# NEWLED.net
KiCad netlist of a schematic drawn in Altium Designer
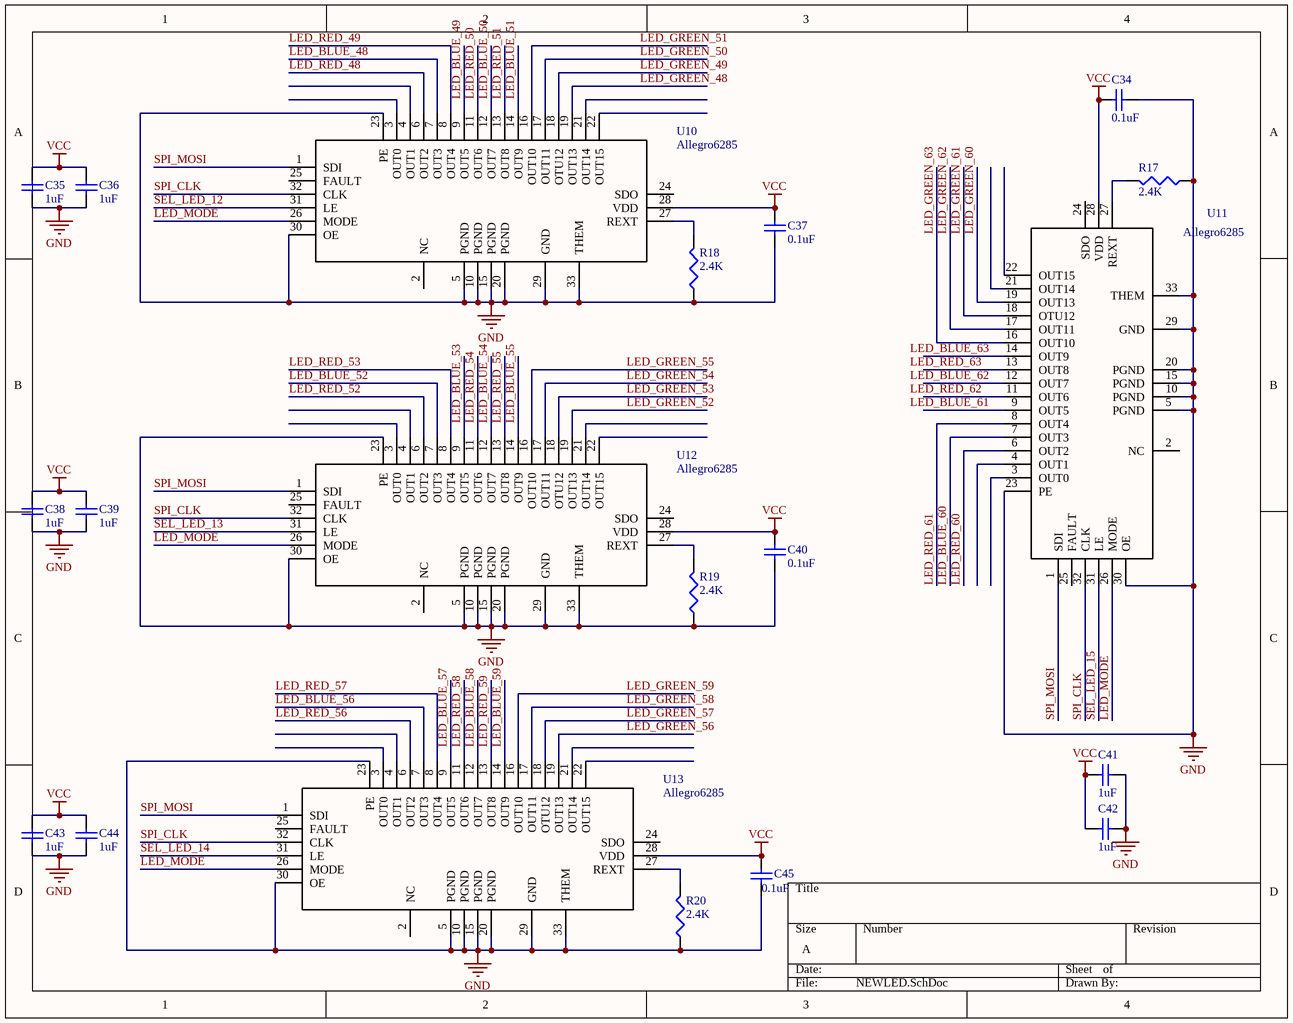
[diagram p0: NEWLED.SchDoc]

(export (version "E")
  (design (tool "Eeschema 10.0.6"))
  (components
    (comp (ref "C34")
      (value "0.1uF")
      (footprint "CAPC1005L")
      (description "Capacitor (Semiconductor SIM Model)")
      (fields (field (name "Comment") "Cap Semi") (field (name "PUBLISHER") "Altium Limited"))
      (libsource (lib "Miscellaneous Devices") (part "Cap Semi"))
    )
    (comp (ref "C35")
      (value "1uF")
      (footprint "CAPC1608L")
      (description "Capacitor (Semiconductor SIM Model)")
      (fields (field (name "Comment") "Cap Semi") (field (name "PUBLISHER") "Altium Limited"))
      (libsource (lib "Miscellaneous Devices") (part "Cap Semi"))
    )
    (comp (ref "C36")
      (value "1uF")
      (footprint "CAPC1608L")
      (description "Capacitor (Semiconductor SIM Model)")
      (fields (field (name "Comment") "Cap Semi") (field (name "PUBLISHER") "Altium Limited"))
      (libsource (lib "Miscellaneous Devices") (part "Cap Semi"))
    )
    (comp (ref "C37")
      (value "0.1uF")
      (footprint "CAPC1005L")
      (description "Capacitor (Semiconductor SIM Model)")
      (fields (field (name "Comment") "Cap Semi") (field (name "PUBLISHER") "Altium Limited"))
      (libsource (lib "Miscellaneous Devices") (part "Cap Semi"))
    )
    (comp (ref "C38")
      (value "1uF")
      (footprint "CAPC1608L")
      (description "Capacitor (Semiconductor SIM Model)")
      (fields (field (name "Comment") "Cap Semi") (field (name "PUBLISHER") "Altium Limited"))
      (libsource (lib "Miscellaneous Devices") (part "Cap Semi"))
    )
    (comp (ref "C39")
      (value "1uF")
      (footprint "CAPC1608L")
      (description "Capacitor (Semiconductor SIM Model)")
      (fields (field (name "Comment") "Cap Semi") (field (name "PUBLISHER") "Altium Limited"))
      (libsource (lib "Miscellaneous Devices") (part "Cap Semi"))
    )
    (comp (ref "C40")
      (value "0.1uF")
      (footprint "CAPC1005L")
      (description "Capacitor (Semiconductor SIM Model)")
      (fields (field (name "Comment") "Cap Semi") (field (name "PUBLISHER") "Altium Limited"))
      (libsource (lib "Miscellaneous Devices") (part "Cap Semi"))
    )
    (comp (ref "C41")
      (value "1uF")
      (footprint "CAPC1608L")
      (description "Capacitor (Semiconductor SIM Model)")
      (fields (field (name "Comment") "Cap Semi") (field (name "PUBLISHER") "Altium Limited"))
      (libsource (lib "Miscellaneous Devices") (part "Cap Semi"))
    )
    (comp (ref "C42")
      (value "1uF")
      (footprint "CAPC1608L")
      (description "Capacitor (Semiconductor SIM Model)")
      (fields (field (name "Comment") "Cap Semi") (field (name "PUBLISHER") "Altium Limited"))
      (libsource (lib "Miscellaneous Devices") (part "Cap Semi"))
    )
    (comp (ref "C43")
      (value "1uF")
      (footprint "CAPC1608L")
      (description "Capacitor (Semiconductor SIM Model)")
      (fields (field (name "Comment") "Cap Semi") (field (name "PUBLISHER") "Altium Limited"))
      (libsource (lib "Miscellaneous Devices") (part "Cap Semi"))
    )
    (comp (ref "C44")
      (value "1uF")
      (footprint "CAPC1608L")
      (description "Capacitor (Semiconductor SIM Model)")
      (fields (field (name "Comment") "Cap Semi") (field (name "PUBLISHER") "Altium Limited"))
      (libsource (lib "Miscellaneous Devices") (part "Cap Semi"))
    )
    (comp (ref "C45")
      (value "0.1uF")
      (footprint "CAPC1005L")
      (description "Capacitor (Semiconductor SIM Model)")
      (fields (field (name "Comment") "Cap Semi") (field (name "PUBLISHER") "Altium Limited"))
      (libsource (lib "Miscellaneous Devices") (part "Cap Semi"))
    )
    (comp (ref "R17")
      (value "2.4K")
      (footprint "RESC1608L")
      (description "Resistor")
      (fields (field (name "Comment") "Res3") (field (name "PUBLISHER") "Altium Limited"))
      (libsource (lib "Miscellaneous Devices") (part "Res3"))
    )
    (comp (ref "R18")
      (value "2.4K")
      (footprint "RESC1608L")
      (description "Resistor")
      (fields (field (name "Comment") "Res3") (field (name "PUBLISHER") "Altium Limited"))
      (libsource (lib "Miscellaneous Devices") (part "Res3"))
    )
    (comp (ref "R19")
      (value "2.4K")
      (footprint "RESC1608L")
      (description "Resistor")
      (fields (field (name "Comment") "Res3") (field (name "PUBLISHER") "Altium Limited"))
      (libsource (lib "Miscellaneous Devices") (part "Res3"))
    )
    (comp (ref "R20")
      (value "2.4K")
      (footprint "RESC1608L")
      (description "Resistor")
      (fields (field (name "Comment") "Res3") (field (name "PUBLISHER") "Altium Limited"))
      (libsource (lib "Miscellaneous Devices") (part "Res3"))
    )
    (comp (ref "U10")
      (value "Allegro6285")
      (footprint "QFN-32")
      (libsource (lib "mrone") (part "Allegro6285"))
    )
    (comp (ref "U11")
      (value "Allegro6285")
      (footprint "QFN-32")
      (libsource (lib "mrone") (part "Allegro6285"))
    )
    (comp (ref "U12")
      (value "Allegro6285")
      (footprint "QFN-32")
      (libsource (lib "mrone") (part "Allegro6285"))
    )
    (comp (ref "U13")
      (value "Allegro6285")
      (footprint "QFN-32")
      (libsource (lib "mrone") (part "Allegro6285"))
    )
  )
  (nets
    (net (code "1") (name "/LED_BLUE_48") (class "Default")
      (node (ref "U10") (pin "7") (pinfunction "OUT3_7") (pintype "passive"))
    )
    (net (code "2") (name "/LED_BLUE_49") (class "Default")
      (node (ref "U10") (pin "9") (pinfunction "OUT5_9") (pintype "passive"))
    )
    (net (code "3") (name "/LED_BLUE_50") (class "Default")
      (node (ref "U10") (pin "12") (pinfunction "OUT7_12") (pintype "passive"))
    )
    (net (code "4") (name "/LED_BLUE_51") (class "Default")
      (node (ref "U10") (pin "14") (pinfunction "OUT9_14") (pintype "passive"))
    )
    (net (code "5") (name "/LED_BLUE_52") (class "Default")
      (node (ref "U12") (pin "7") (pinfunction "OUT3_7") (pintype "passive"))
    )
    (net (code "6") (name "/LED_BLUE_53") (class "Default")
      (node (ref "U12") (pin "9") (pinfunction "OUT5_9") (pintype "passive"))
    )
    (net (code "7") (name "/LED_BLUE_54") (class "Default")
      (node (ref "U12") (pin "12") (pinfunction "OUT7_12") (pintype "passive"))
    )
    (net (code "8") (name "/LED_BLUE_55") (class "Default")
      (node (ref "U12") (pin "14") (pinfunction "OUT9_14") (pintype "passive"))
    )
    (net (code "9") (name "/LED_BLUE_56") (class "Default")
      (node (ref "U13") (pin "7") (pinfunction "OUT3_7") (pintype "passive"))
    )
    (net (code "10") (name "/LED_BLUE_57") (class "Default")
      (node (ref "U13") (pin "9") (pinfunction "OUT5_9") (pintype "passive"))
    )
    (net (code "11") (name "/LED_BLUE_58") (class "Default")
      (node (ref "U13") (pin "12") (pinfunction "OUT7_12") (pintype "passive"))
    )
    (net (code "12") (name "/LED_BLUE_59") (class "Default")
      (node (ref "U13") (pin "14") (pinfunction "OUT9_14") (pintype "passive"))
    )
    (net (code "13") (name "/LED_BLUE_60") (class "Default")
      (node (ref "U11") (pin "7") (pinfunction "OUT3_7") (pintype "passive"))
    )
    (net (code "17") (name "/LED_GREEN_48") (class "Default")
      (node (ref "U10") (pin "19") (pinfunction "OUT13_19") (pintype "passive"))
    )
    (net (code "18") (name "/LED_GREEN_49") (class "Default")
      (node (ref "U10") (pin "18") (pinfunction "OTU12_18") (pintype "passive"))
    )
    (net (code "19") (name "/LED_GREEN_50") (class "Default")
      (node (ref "U10") (pin "17") (pinfunction "OUT11_17") (pintype "passive"))
    )
    (net (code "20") (name "/LED_GREEN_51") (class "Default")
      (node (ref "U10") (pin "16") (pinfunction "OUT10_16") (pintype "passive"))
    )
    (net (code "21") (name "/LED_GREEN_52") (class "Default")
      (node (ref "U12") (pin "19") (pinfunction "OUT13_19") (pintype "passive"))
    )
    (net (code "22") (name "/LED_GREEN_53") (class "Default")
      (node (ref "U12") (pin "18") (pinfunction "OTU12_18") (pintype "passive"))
    )
    (net (code "23") (name "/LED_GREEN_54") (class "Default")
      (node (ref "U12") (pin "17") (pinfunction "OUT11_17") (pintype "passive"))
    )
    (net (code "24") (name "/LED_GREEN_55") (class "Default")
      (node (ref "U12") (pin "16") (pinfunction "OUT10_16") (pintype "passive"))
    )
    (net (code "25") (name "/LED_GREEN_56") (class "Default")
      (node (ref "U13") (pin "19") (pinfunction "OUT13_19") (pintype "passive"))
    )
    (net (code "26") (name "/LED_GREEN_57") (class "Default")
      (node (ref "U13") (pin "18") (pinfunction "OTU12_18") (pintype "passive"))
    )
    (net (code "27") (name "/LED_GREEN_58") (class "Default")
      (node (ref "U13") (pin "17") (pinfunction "OUT11_17") (pintype "passive"))
    )
    (net (code "28") (name "/LED_GREEN_59") (class "Default")
      (node (ref "U13") (pin "16") (pinfunction "OUT10_16") (pintype "passive"))
    )
    (net (code "29") (name "/LED_GREEN_60") (class "Default")
      (node (ref "U11") (pin "19") (pinfunction "OUT13_19") (pintype "passive"))
    )
    (net (code "30") (name "/LED_GREEN_61") (class "Default")
      (node (ref "U11") (pin "18") (pinfunction "OTU12_18") (pintype "passive"))
    )
    (net (code "31") (name "/LED_GREEN_62") (class "Default")
      (node (ref "U11") (pin "17") (pinfunction "OUT11_17") (pintype "passive"))
    )
    (net (code "32") (name "/LED_GREEN_63") (class "Default")
      (node (ref "U11") (pin "16") (pinfunction "OUT10_16") (pintype "passive"))
    )
    (net (code "33") (name "/LED_MODE") (class "Default")
      (node (ref "U10") (pin "26") (pinfunction "MODE_26") (pintype "passive"))
      (node (ref "U11") (pin "26") (pinfunction "MODE_26") (pintype "passive"))
      (node (ref "U12") (pin "26") (pinfunction "MODE_26") (pintype "passive"))
      (node (ref "U13") (pin "26") (pinfunction "MODE_26") (pintype "passive"))
    )
    (net (code "34") (name "/LED_RED_48") (class "Default")
      (node (ref "U10") (pin "6") (pinfunction "OUT2_6") (pintype "passive"))
    )
    (net (code "35") (name "/LED_RED_49") (class "Default")
      (node (ref "U10") (pin "8") (pinfunction "OUT4_8") (pintype "passive"))
    )
    (net (code "36") (name "/LED_RED_50") (class "Default")
      (node (ref "U10") (pin "11") (pinfunction "OUT6_11") (pintype "passive"))
    )
    (net (code "37") (name "/LED_RED_51") (class "Default")
      (node (ref "U10") (pin "13") (pinfunction "OUT8_13") (pintype "passive"))
    )
    (net (code "38") (name "/LED_RED_52") (class "Default")
      (node (ref "U12") (pin "6") (pinfunction "OUT2_6") (pintype "passive"))
    )
    (net (code "39") (name "/LED_RED_53") (class "Default")
      (node (ref "U12") (pin "8") (pinfunction "OUT4_8") (pintype "passive"))
    )
    (net (code "40") (name "/LED_RED_54") (class "Default")
      (node (ref "U12") (pin "11") (pinfunction "OUT6_11") (pintype "passive"))
    )
    (net (code "41") (name "/LED_RED_55") (class "Default")
      (node (ref "U12") (pin "13") (pinfunction "OUT8_13") (pintype "passive"))
    )
    (net (code "42") (name "/LED_RED_56") (class "Default")
      (node (ref "U13") (pin "6") (pinfunction "OUT2_6") (pintype "passive"))
    )
    (net (code "43") (name "/LED_RED_57") (class "Default")
      (node (ref "U13") (pin "8") (pinfunction "OUT4_8") (pintype "passive"))
    )
    (net (code "44") (name "/LED_RED_58") (class "Default")
      (node (ref "U13") (pin "11") (pinfunction "OUT6_11") (pintype "passive"))
    )
    (net (code "45") (name "/LED_RED_59") (class "Default")
      (node (ref "U13") (pin "13") (pinfunction "OUT8_13") (pintype "passive"))
    )
    (net (code "46") (name "/LED_RED_60") (class "Default")
      (node (ref "U11") (pin "6") (pinfunction "OUT2_6") (pintype "passive"))
    )
    (net (code "47") (name "/LED_RED_61") (class "Default")
      (node (ref "U11") (pin "8") (pinfunction "OUT4_8") (pintype "passive"))
    )
    (net (code "50") (name "/SEL_LED_12") (class "Default")
      (node (ref "U10") (pin "31") (pinfunction "LE_31") (pintype "passive"))
    )
    (net (code "51") (name "/SEL_LED_13") (class "Default")
      (node (ref "U12") (pin "31") (pinfunction "LE_31") (pintype "passive"))
    )
    (net (code "52") (name "/SEL_LED_14") (class "Default")
      (node (ref "U13") (pin "31") (pinfunction "LE_31") (pintype "passive"))
    )
    (net (code "53") (name "/SEL_LED_15") (class "Default")
      (node (ref "U11") (pin "31") (pinfunction "LE_31") (pintype "passive"))
    )
    (net (code "54") (name "/SPI_CLK") (class "Default")
      (node (ref "U10") (pin "32") (pinfunction "CLK_32") (pintype "passive"))
      (node (ref "U11") (pin "32") (pinfunction "CLK_32") (pintype "passive"))
      (node (ref "U12") (pin "32") (pinfunction "CLK_32") (pintype "passive"))
      (node (ref "U13") (pin "32") (pinfunction "CLK_32") (pintype "passive"))
    )
    (net (code "55") (name "/SPI_MOSI") (class "Default")
      (node (ref "U10") (pin "1") (pinfunction "SDI_1") (pintype "passive"))
      (node (ref "U11") (pin "1") (pinfunction "SDI_1") (pintype "passive"))
      (node (ref "U12") (pin "1") (pinfunction "SDI_1") (pintype "passive"))
      (node (ref "U13") (pin "1") (pinfunction "SDI_1") (pintype "passive"))
    )
    (net (code "56") (name "GND") (class "Default")
      (node (ref "C34") (pin "1") (pinfunction "1_1") (pintype "passive"))
      (node (ref "C35") (pin "1") (pinfunction "1_1") (pintype "passive"))
      (node (ref "C36") (pin "1") (pinfunction "1_1") (pintype "passive"))
      (node (ref "C37") (pin "1") (pinfunction "1_1") (pintype "passive"))
      (node (ref "C38") (pin "1") (pinfunction "1_1") (pintype "passive"))
      (node (ref "C39") (pin "1") (pinfunction "1_1") (pintype "passive"))
      (node (ref "C40") (pin "1") (pinfunction "1_1") (pintype "passive"))
      (node (ref "C41") (pin "1") (pinfunction "1_1") (pintype "passive"))
      (node (ref "C42") (pin "1") (pinfunction "1_1") (pintype "passive"))
      (node (ref "C43") (pin "1") (pinfunction "1_1") (pintype "passive"))
      (node (ref "C44") (pin "1") (pinfunction "1_1") (pintype "passive"))
      (node (ref "C45") (pin "1") (pinfunction "1_1") (pintype "passive"))
      (node (ref "R17") (pin "1") (pinfunction "1_1") (pintype "passive"))
      (node (ref "R18") (pin "1") (pinfunction "1_1") (pintype "passive"))
      (node (ref "R19") (pin "1") (pinfunction "1_1") (pintype "passive"))
      (node (ref "R20") (pin "1") (pinfunction "1_1") (pintype "passive"))
      (node (ref "U10") (pin "10") (pinfunction "PGND_10") (pintype "passive"))
      (node (ref "U10") (pin "15") (pinfunction "PGND_15") (pintype "passive"))
      (node (ref "U10") (pin "20") (pinfunction "PGND_20") (pintype "passive"))
      (node (ref "U10") (pin "23") (pinfunction "PE_23") (pintype "passive"))
      (node (ref "U10") (pin "29") (pinfunction "GND_29") (pintype "passive"))
      (node (ref "U10") (pin "30") (pinfunction "OE_30") (pintype "passive"))
      (node (ref "U10") (pin "33") (pinfunction "THEM_33") (pintype "passive"))
      (node (ref "U10") (pin "5") (pinfunction "PGND_5") (pintype "passive"))
      (node (ref "U11") (pin "10") (pinfunction "PGND_10") (pintype "passive"))
      (node (ref "U11") (pin "15") (pinfunction "PGND_15") (pintype "passive"))
      (node (ref "U11") (pin "20") (pinfunction "PGND_20") (pintype "passive"))
      (node (ref "U11") (pin "23") (pinfunction "PE_23") (pintype "passive"))
      (node (ref "U11") (pin "29") (pinfunction "GND_29") (pintype "passive"))
      (node (ref "U11") (pin "30") (pinfunction "OE_30") (pintype "passive"))
      (node (ref "U11") (pin "33") (pinfunction "THEM_33") (pintype "passive"))
      (node (ref "U11") (pin "5") (pinfunction "PGND_5") (pintype "passive"))
      (node (ref "U12") (pin "10") (pinfunction "PGND_10") (pintype "passive"))
      (node (ref "U12") (pin "15") (pinfunction "PGND_15") (pintype "passive"))
      (node (ref "U12") (pin "20") (pinfunction "PGND_20") (pintype "passive"))
      (node (ref "U12") (pin "23") (pinfunction "PE_23") (pintype "passive"))
      (node (ref "U12") (pin "29") (pinfunction "GND_29") (pintype "passive"))
      (node (ref "U12") (pin "30") (pinfunction "OE_30") (pintype "passive"))
      (node (ref "U12") (pin "33") (pinfunction "THEM_33") (pintype "passive"))
      (node (ref "U12") (pin "5") (pinfunction "PGND_5") (pintype "passive"))
      (node (ref "U13") (pin "10") (pinfunction "PGND_10") (pintype "passive"))
      (node (ref "U13") (pin "15") (pinfunction "PGND_15") (pintype "passive"))
      (node (ref "U13") (pin "20") (pinfunction "PGND_20") (pintype "passive"))
      (node (ref "U13") (pin "23") (pinfunction "PE_23") (pintype "passive"))
      (node (ref "U13") (pin "29") (pinfunction "GND_29") (pintype "passive"))
      (node (ref "U13") (pin "30") (pinfunction "OE_30") (pintype "passive"))
      (node (ref "U13") (pin "33") (pinfunction "THEM_33") (pintype "passive"))
      (node (ref "U13") (pin "5") (pinfunction "PGND_5") (pintype "passive"))
    )
    (net (code "57") (name "Net-(U10-REXT)") (class "Default")
      (node (ref "R18") (pin "2") (pinfunction "2_2") (pintype "passive"))
      (node (ref "U10") (pin "27") (pinfunction "REXT_27") (pintype "passive"))
    )
    (net (code "58") (name "Net-(U11-REXT)") (class "Default")
      (node (ref "R17") (pin "2") (pinfunction "2_2") (pintype "passive"))
      (node (ref "U11") (pin "27") (pinfunction "REXT_27") (pintype "passive"))
    )
    (net (code "59") (name "Net-(U12-REXT)") (class "Default")
      (node (ref "R19") (pin "2") (pinfunction "2_2") (pintype "passive"))
      (node (ref "U12") (pin "27") (pinfunction "REXT_27") (pintype "passive"))
    )
    (net (code "60") (name "Net-(U13-REXT)") (class "Default")
      (node (ref "R20") (pin "2") (pinfunction "2_2") (pintype "passive"))
      (node (ref "U13") (pin "27") (pinfunction "REXT_27") (pintype "passive"))
    )
    (net (code "61") (name "VCC") (class "Default")
      (node (ref "C34") (pin "2") (pinfunction "2_2") (pintype "passive"))
      (node (ref "C35") (pin "2") (pinfunction "2_2") (pintype "passive"))
      (node (ref "C36") (pin "2") (pinfunction "2_2") (pintype "passive"))
      (node (ref "C37") (pin "2") (pinfunction "2_2") (pintype "passive"))
      (node (ref "C38") (pin "2") (pinfunction "2_2") (pintype "passive"))
      (node (ref "C39") (pin "2") (pinfunction "2_2") (pintype "passive"))
      (node (ref "C40") (pin "2") (pinfunction "2_2") (pintype "passive"))
      (node (ref "C41") (pin "2") (pinfunction "2_2") (pintype "passive"))
      (node (ref "C42") (pin "2") (pinfunction "2_2") (pintype "passive"))
      (node (ref "C43") (pin "2") (pinfunction "2_2") (pintype "passive"))
      (node (ref "C44") (pin "2") (pinfunction "2_2") (pintype "passive"))
      (node (ref "C45") (pin "2") (pinfunction "2_2") (pintype "passive"))
      (node (ref "U10") (pin "28") (pinfunction "VDD_28") (pintype "passive"))
      (node (ref "U11") (pin "28") (pinfunction "VDD_28") (pintype "passive"))
      (node (ref "U12") (pin "28") (pinfunction "VDD_28") (pintype "passive"))
      (node (ref "U13") (pin "28") (pinfunction "VDD_28") (pintype "passive"))
    )
    (net (code "62") (name "unconnected-(U10-FAULT-Pad25)") (class "Default")
      (node (ref "U10") (pin "25") (pinfunction "FAULT_25") (pintype "passive"))
    )
    (net (code "63") (name "unconnected-(U10-NC-Pad2)") (class "Default")
      (node (ref "U10") (pin "2") (pinfunction "NC_2") (pintype "passive"))
    )
    (net (code "64") (name "unconnected-(U10-OUT0-Pad3)") (class "Default")
      (node (ref "U10") (pin "3") (pinfunction "OUT0_3") (pintype "passive"))
    )
    (net (code "65") (name "unconnected-(U10-OUT1-Pad4)") (class "Default")
      (node (ref "U10") (pin "4") (pinfunction "OUT1_4") (pintype "passive"))
    )
    (net (code "66") (name "unconnected-(U10-OUT14-Pad21)") (class "Default")
      (node (ref "U10") (pin "21") (pinfunction "OUT14_21") (pintype "passive"))
    )
    (net (code "67") (name "unconnected-(U10-OUT15-Pad22)") (class "Default")
      (node (ref "U10") (pin "22") (pinfunction "OUT15_22") (pintype "passive"))
    )
    (net (code "68") (name "unconnected-(U10-SDO-Pad24)") (class "Default")
      (node (ref "U10") (pin "24") (pinfunction "SDO_24") (pintype "passive"))
    )
    (net (code "69") (name "unconnected-(U11-FAULT-Pad25)") (class "Default")
      (node (ref "U11") (pin "25") (pinfunction "FAULT_25") (pintype "passive"))
    )
    (net (code "70") (name "unconnected-(U11-NC-Pad2)") (class "Default")
      (node (ref "U11") (pin "2") (pinfunction "NC_2") (pintype "passive"))
    )
    (net (code "71") (name "unconnected-(U11-OUT0-Pad3)") (class "Default")
      (node (ref "U11") (pin "3") (pinfunction "OUT0_3") (pintype "passive"))
    )
    (net (code "72") (name "unconnected-(U11-OUT1-Pad4)") (class "Default")
      (node (ref "U11") (pin "4") (pinfunction "OUT1_4") (pintype "passive"))
    )
    (net (code "73") (name "unconnected-(U11-OUT5-Pad9)") (class "Default")
      (node (ref "U11") (pin "9") (pinfunction "OUT5_9") (pintype "passive"))
    )
    (net (code "74") (name "unconnected-(U11-OUT6-Pad11)") (class "Default")
      (node (ref "U11") (pin "11") (pinfunction "OUT6_11") (pintype "passive"))
    )
    (net (code "75") (name "unconnected-(U11-OUT7-Pad12)") (class "Default")
      (node (ref "U11") (pin "12") (pinfunction "OUT7_12") (pintype "passive"))
    )
    (net (code "76") (name "unconnected-(U11-OUT8-Pad13)") (class "Default")
      (node (ref "U11") (pin "13") (pinfunction "OUT8_13") (pintype "passive"))
    )
    (net (code "77") (name "unconnected-(U11-OUT9-Pad14)") (class "Default")
      (node (ref "U11") (pin "14") (pinfunction "OUT9_14") (pintype "passive"))
    )
    (net (code "78") (name "unconnected-(U11-OUT14-Pad21)") (class "Default")
      (node (ref "U11") (pin "21") (pinfunction "OUT14_21") (pintype "passive"))
    )
    (net (code "79") (name "unconnected-(U11-OUT15-Pad22)") (class "Default")
      (node (ref "U11") (pin "22") (pinfunction "OUT15_22") (pintype "passive"))
    )
    (net (code "80") (name "unconnected-(U11-SDO-Pad24)") (class "Default")
      (node (ref "U11") (pin "24") (pinfunction "SDO_24") (pintype "passive"))
    )
    (net (code "81") (name "unconnected-(U12-FAULT-Pad25)") (class "Default")
      (node (ref "U12") (pin "25") (pinfunction "FAULT_25") (pintype "passive"))
    )
    (net (code "82") (name "unconnected-(U12-NC-Pad2)") (class "Default")
      (node (ref "U12") (pin "2") (pinfunction "NC_2") (pintype "passive"))
    )
    (net (code "83") (name "unconnected-(U12-OUT0-Pad3)") (class "Default")
      (node (ref "U12") (pin "3") (pinfunction "OUT0_3") (pintype "passive"))
    )
    (net (code "84") (name "unconnected-(U12-OUT1-Pad4)") (class "Default")
      (node (ref "U12") (pin "4") (pinfunction "OUT1_4") (pintype "passive"))
    )
    (net (code "85") (name "unconnected-(U12-OUT14-Pad21)") (class "Default")
      (node (ref "U12") (pin "21") (pinfunction "OUT14_21") (pintype "passive"))
    )
    (net (code "86") (name "unconnected-(U12-OUT15-Pad22)") (class "Default")
      (node (ref "U12") (pin "22") (pinfunction "OUT15_22") (pintype "passive"))
    )
    (net (code "87") (name "unconnected-(U12-SDO-Pad24)") (class "Default")
      (node (ref "U12") (pin "24") (pinfunction "SDO_24") (pintype "passive"))
    )
    (net (code "88") (name "unconnected-(U13-FAULT-Pad25)") (class "Default")
      (node (ref "U13") (pin "25") (pinfunction "FAULT_25") (pintype "passive"))
    )
    (net (code "89") (name "unconnected-(U13-NC-Pad2)") (class "Default")
      (node (ref "U13") (pin "2") (pinfunction "NC_2") (pintype "passive"))
    )
    (net (code "90") (name "unconnected-(U13-OUT0-Pad3)") (class "Default")
      (node (ref "U13") (pin "3") (pinfunction "OUT0_3") (pintype "passive"))
    )
    (net (code "91") (name "unconnected-(U13-OUT1-Pad4)") (class "Default")
      (node (ref "U13") (pin "4") (pinfunction "OUT1_4") (pintype "passive"))
    )
    (net (code "92") (name "unconnected-(U13-OUT14-Pad21)") (class "Default")
      (node (ref "U13") (pin "21") (pinfunction "OUT14_21") (pintype "passive"))
    )
    (net (code "93") (name "unconnected-(U13-OUT15-Pad22)") (class "Default")
      (node (ref "U13") (pin "22") (pinfunction "OUT15_22") (pintype "passive"))
    )
    (net (code "94") (name "unconnected-(U13-SDO-Pad24)") (class "Default")
      (node (ref "U13") (pin "24") (pinfunction "SDO_24") (pintype "passive"))
    )
  )
)
